# usb.net
KiCad netlist of a schematic drawn in Altium Designer
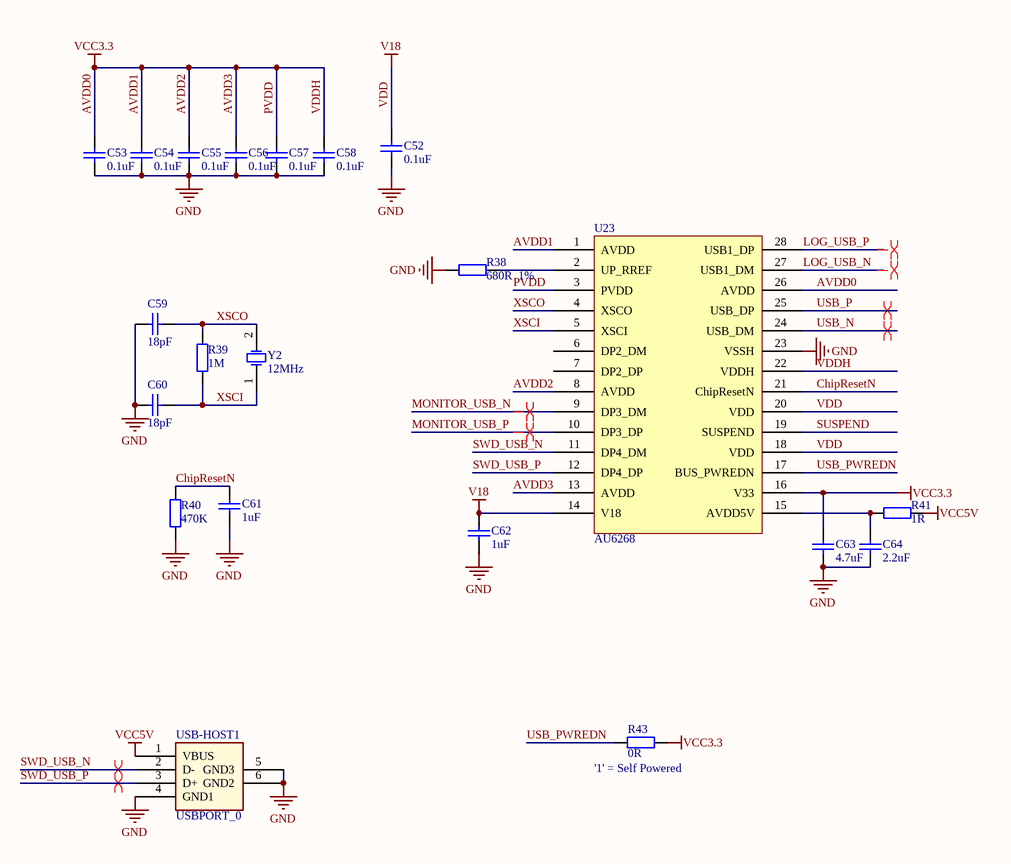
[diagram p0: usb.SchDoc]

(export (version "E")
  (design (tool "Eeschema 10.0.6"))
  (components
    (comp (ref "C52")
      (value "0.1uF")
      (footprint "0603_C")
      (description "贴片电容，0603")
      (libsource (lib "stm8l052r8t6开发板") (part "Cap"))
    )
    (comp (ref "C53")
      (value "0.1uF")
      (footprint "0603_C")
      (description "贴片电容，0603")
      (libsource (lib "stm8l052r8t6开发板") (part "Cap"))
    )
    (comp (ref "C54")
      (value "0.1uF")
      (footprint "0603_C")
      (description "贴片电容，0603")
      (libsource (lib "stm8l052r8t6开发板") (part "Cap"))
    )
    (comp (ref "C55")
      (value "0.1uF")
      (footprint "0603_C")
      (description "贴片电容，0603")
      (libsource (lib "stm8l052r8t6开发板") (part "Cap"))
    )
    (comp (ref "C56")
      (value "0.1uF")
      (footprint "0603_C")
      (description "贴片电容，0603")
      (libsource (lib "stm8l052r8t6开发板") (part "Cap"))
    )
    (comp (ref "C57")
      (value "0.1uF")
      (footprint "0603_C")
      (description "贴片电容，0603")
      (libsource (lib "stm8l052r8t6开发板") (part "Cap"))
    )
    (comp (ref "C58")
      (value "0.1uF")
      (footprint "0603_C")
      (description "贴片电容，0603")
      (libsource (lib "stm8l052r8t6开发板") (part "Cap"))
    )
    (comp (ref "C59")
      (value "18pF")
      (footprint "0603_C")
      (description "贴片电容，0603")
      (libsource (lib "stm8l052r8t6开发板") (part "Cap"))
    )
    (comp (ref "C60")
      (value "18pF")
      (footprint "0603_C")
      (description "贴片电容，0603")
      (libsource (lib "stm8l052r8t6开发板") (part "Cap"))
    )
    (comp (ref "C61")
      (value "1uF")
      (footprint "0603_C")
      (description "贴片电容，0603")
      (libsource (lib "stm8l052r8t6开发板") (part "Cap"))
    )
    (comp (ref "C62")
      (value "1uF")
      (footprint "0603_C")
      (description "贴片电容，0603")
      (libsource (lib "stm8l052r8t6开发板") (part "Cap"))
    )
    (comp (ref "C63")
      (value "4.7uF")
      (footprint "0603_C")
      (description "贴片电容，0603")
      (libsource (lib "stm8l052r8t6开发板") (part "Cap"))
    )
    (comp (ref "C64")
      (value "2.2uF")
      (footprint "0603_C")
      (description "贴片电容，0603")
      (libsource (lib "stm8l052r8t6开发板") (part "Cap"))
    )
    (comp (ref "R38")
      (value "680R  1%")
      (footprint "0603_R")
      (description "贴片电阻，0603")
      (libsource (lib "extendBoard") (part "Res2"))
    )
    (comp (ref "R39")
      (value "1M")
      (footprint "0603_R")
      (description "贴片电阻，0603")
      (libsource (lib "") (part "Res2_2"))
    )
    (comp (ref "R40")
      (value "470K")
      (footprint "0603_R")
      (description "贴片电阻，0603")
      (libsource (lib "") (part "Res2_2"))
    )
    (comp (ref "R41")
      (value "1R")
      (footprint "0603_R")
      (description "贴片电阻，0603")
      (libsource (lib "extendBoard") (part "Res2"))
    )
    (comp (ref "R43")
      (value "0R")
      (footprint "0603_R")
      (description "贴片电阻，0603")
      (libsource (lib "") (part "Res2_1"))
    )
    (comp (ref "U23")
      (value "AU6268")
      (footprint "SSOP-28_208mil")
      (description "AU6268,SSOP28封装")
      (libsource (lib "stm8l052r8t6开发板") (part "AU6268"))
    )
    (comp (ref "USB-HOST1")
      (value "USBPORT_0")
      (footprint "USB-A-TH_USB-DIP-04F-S1-B1-Y2")
      (description "USB - A 插座 ,直角,292303-1")
      (libsource (lib "stm8l052r8t6开发板") (part "USBPORT_0"))
    )
    (comp (ref "Y2")
      (value "12MHz")
      (footprint "LC-HC-49SMD")
      (description "贴片晶振，49SMD")
      (libsource (lib "stm8l052r8t6开发板") (part "XTAL"))
    )
  )
  (nets
    (net (code "1") (name "/ChipResetN") (class "Default")
      (node (ref "C61") (pin "2") (pinfunction "2_2") (pintype "passive"))
      (node (ref "R40") (pin "2") (pinfunction "2_2") (pintype "passive"))
      (node (ref "U23") (pin "21") (pinfunction "ChipResetN_21") (pintype "passive"))
    )
    (net (code "2") (name "/LOG_USB_N") (class "Default")
      (node (ref "U23") (pin "27") (pinfunction "USB1_DM_27") (pintype "passive"))
    )
    (net (code "3") (name "/LOG_USB_P") (class "Default")
      (node (ref "U23") (pin "28") (pinfunction "USB1_DP_28") (pintype "passive"))
    )
    (net (code "4") (name "/MONITOR_USB_N") (class "Default")
      (node (ref "U23") (pin "9") (pinfunction "DP3_DM_9") (pintype "passive"))
    )
    (net (code "5") (name "/MONITOR_USB_P") (class "Default")
      (node (ref "U23") (pin "10") (pinfunction "DP3_DP_10") (pintype "passive"))
    )
    (net (code "6") (name "/SUSPEND") (class "Default")
      (node (ref "U23") (pin "19") (pinfunction "SUSPEND_19") (pintype "passive"))
    )
    (net (code "7") (name "/SWD_USB_N") (class "Default")
      (node (ref "U23") (pin "11") (pinfunction "DP4_DM_11") (pintype "passive"))
      (node (ref "USB-HOST1") (pin "2") (pinfunction "D-_2") (pintype "passive"))
    )
    (net (code "8") (name "/SWD_USB_P") (class "Default")
      (node (ref "U23") (pin "12") (pinfunction "DP4_DP_12") (pintype "passive"))
      (node (ref "USB-HOST1") (pin "3") (pinfunction "D+_3") (pintype "passive"))
    )
    (net (code "9") (name "/USB_N") (class "Default")
      (node (ref "U23") (pin "24") (pinfunction "USB_DM_24") (pintype "passive"))
    )
    (net (code "10") (name "/USB_P") (class "Default")
      (node (ref "U23") (pin "25") (pinfunction "USB_DP_25") (pintype "passive"))
    )
    (net (code "11") (name "/USB_PWREDN") (class "Default")
      (node (ref "R43") (pin "2") (pinfunction "2_2") (pintype "passive"))
      (node (ref "U23") (pin "17") (pinfunction "BUS_PWREDN_17") (pintype "passive"))
    )
    (net (code "12") (name "/XSCI") (class "Default")
      (node (ref "C60") (pin "1") (pinfunction "1_1") (pintype "passive"))
      (node (ref "R39") (pin "1") (pinfunction "1_1") (pintype "passive"))
      (node (ref "U23") (pin "5") (pinfunction "XSCI_5") (pintype "passive"))
      (node (ref "Y2") (pin "1") (pinfunction "OSC1_1") (pintype "passive"))
    )
    (net (code "13") (name "/XSCO") (class "Default")
      (node (ref "C59") (pin "1") (pinfunction "1_1") (pintype "passive"))
      (node (ref "R39") (pin "2") (pinfunction "2_2") (pintype "passive"))
      (node (ref "U23") (pin "4") (pinfunction "XSCO_4") (pintype "passive"))
      (node (ref "Y2") (pin "2") (pinfunction "OSC2_2") (pintype "passive"))
    )
    (net (code "14") (name "GND") (class "Default")
      (node (ref "C52") (pin "1") (pinfunction "1_1") (pintype "passive"))
      (node (ref "C53") (pin "1") (pinfunction "1_1") (pintype "passive"))
      (node (ref "C54") (pin "1") (pinfunction "1_1") (pintype "passive"))
      (node (ref "C55") (pin "1") (pinfunction "1_1") (pintype "passive"))
      (node (ref "C56") (pin "1") (pinfunction "1_1") (pintype "passive"))
      (node (ref "C57") (pin "1") (pinfunction "1_1") (pintype "passive"))
      (node (ref "C58") (pin "1") (pinfunction "1_1") (pintype "passive"))
      (node (ref "C59") (pin "2") (pinfunction "2_2") (pintype "passive"))
      (node (ref "C60") (pin "2") (pinfunction "2_2") (pintype "passive"))
      (node (ref "C61") (pin "1") (pinfunction "1_1") (pintype "passive"))
      (node (ref "C62") (pin "1") (pinfunction "1_1") (pintype "passive"))
      (node (ref "C63") (pin "1") (pinfunction "1_1") (pintype "passive"))
      (node (ref "C64") (pin "1") (pinfunction "1_1") (pintype "passive"))
      (node (ref "R38") (pin "1") (pinfunction "1_1") (pintype "passive"))
      (node (ref "R40") (pin "1") (pinfunction "1_1") (pintype "passive"))
      (node (ref "U23") (pin "23") (pinfunction "VSSH_23") (pintype "passive"))
      (node (ref "USB-HOST1") (pin "4") (pinfunction "GND1_4") (pintype "passive"))
      (node (ref "USB-HOST1") (pin "5") (pinfunction "GND3_5") (pintype "passive"))
      (node (ref "USB-HOST1") (pin "6") (pinfunction "GND2_6") (pintype "passive"))
    )
    (net (code "15") (name "Net-(U23-AVDD5V)") (class "Default")
      (node (ref "C64") (pin "2") (pinfunction "2_2") (pintype "passive"))
      (node (ref "R41") (pin "1") (pinfunction "1_1") (pintype "passive"))
      (node (ref "U23") (pin "15") (pinfunction "AVDD5V_15") (pintype "passive"))
    )
    (net (code "16") (name "Net-(U23-UP_RREF)") (class "Default")
      (node (ref "R38") (pin "2") (pinfunction "2_2") (pintype "passive"))
      (node (ref "U23") (pin "2") (pinfunction "UP_RREF_2") (pintype "passive"))
    )
    (net (code "17") (name "V18") (class "Default")
      (node (ref "C52") (pin "2") (pinfunction "2_2") (pintype "passive"))
      (node (ref "C62") (pin "2") (pinfunction "2_2") (pintype "passive"))
      (node (ref "U23") (pin "14") (pinfunction "V18_14") (pintype "passive"))
      (node (ref "U23") (pin "18") (pinfunction "VDD_18") (pintype "passive"))
      (node (ref "U23") (pin "20") (pinfunction "VDD_20") (pintype "passive"))
    )
    (net (code "18") (name "VCC3.3") (class "Default")
      (node (ref "C53") (pin "2") (pinfunction "2_2") (pintype "passive"))
      (node (ref "C54") (pin "2") (pinfunction "2_2") (pintype "passive"))
      (node (ref "C55") (pin "2") (pinfunction "2_2") (pintype "passive"))
      (node (ref "C56") (pin "2") (pinfunction "2_2") (pintype "passive"))
      (node (ref "C57") (pin "2") (pinfunction "2_2") (pintype "passive"))
      (node (ref "C58") (pin "2") (pinfunction "2_2") (pintype "passive"))
      (node (ref "C63") (pin "2") (pinfunction "2_2") (pintype "passive"))
      (node (ref "R43") (pin "1") (pinfunction "1_1") (pintype "passive"))
      (node (ref "U23") (pin "1") (pinfunction "AVDD_1") (pintype "passive"))
      (node (ref "U23") (pin "13") (pinfunction "AVDD_13") (pintype "passive"))
      (node (ref "U23") (pin "16") (pinfunction "V33_16") (pintype "passive"))
      (node (ref "U23") (pin "22") (pinfunction "VDDH_22") (pintype "passive"))
      (node (ref "U23") (pin "26") (pinfunction "AVDD_26") (pintype "passive"))
      (node (ref "U23") (pin "3") (pinfunction "PVDD_3") (pintype "passive"))
      (node (ref "U23") (pin "8") (pinfunction "AVDD_8") (pintype "passive"))
    )
    (net (code "19") (name "VCC5V") (class "Default")
      (node (ref "R41") (pin "2") (pinfunction "2_2") (pintype "passive"))
      (node (ref "USB-HOST1") (pin "1") (pinfunction "VBUS_1") (pintype "passive"))
    )
    (net (code "20") (name "unconnected-(U23-DP2_DM-Pad6)") (class "Default")
      (node (ref "U23") (pin "6") (pinfunction "DP2_DM_6") (pintype "passive"))
    )
    (net (code "21") (name "unconnected-(U23-DP2_DP-Pad7)") (class "Default")
      (node (ref "U23") (pin "7") (pinfunction "DP2_DP_7") (pintype "passive"))
    )
  )
)
